# FPGA.net
KiCad netlist of a schematic drawn in Altium Designer
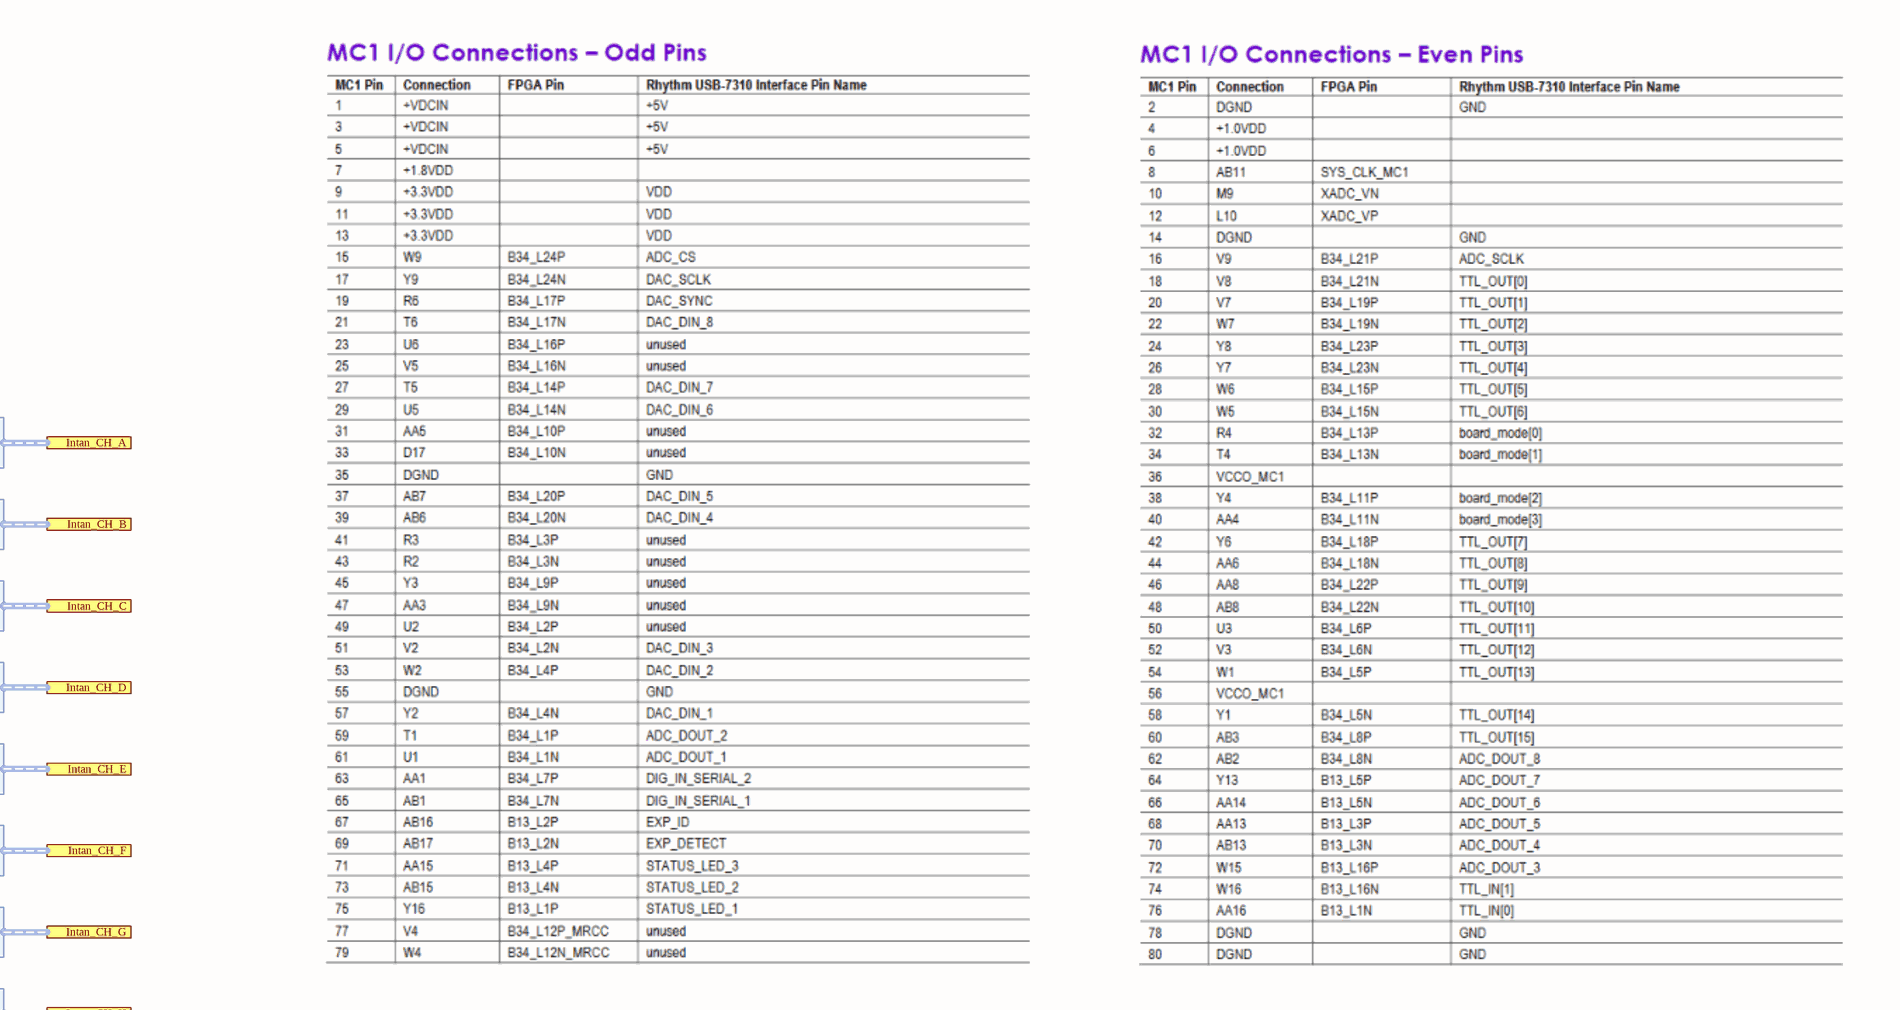
[diagram p0: FPGA.SchDoc, top right]
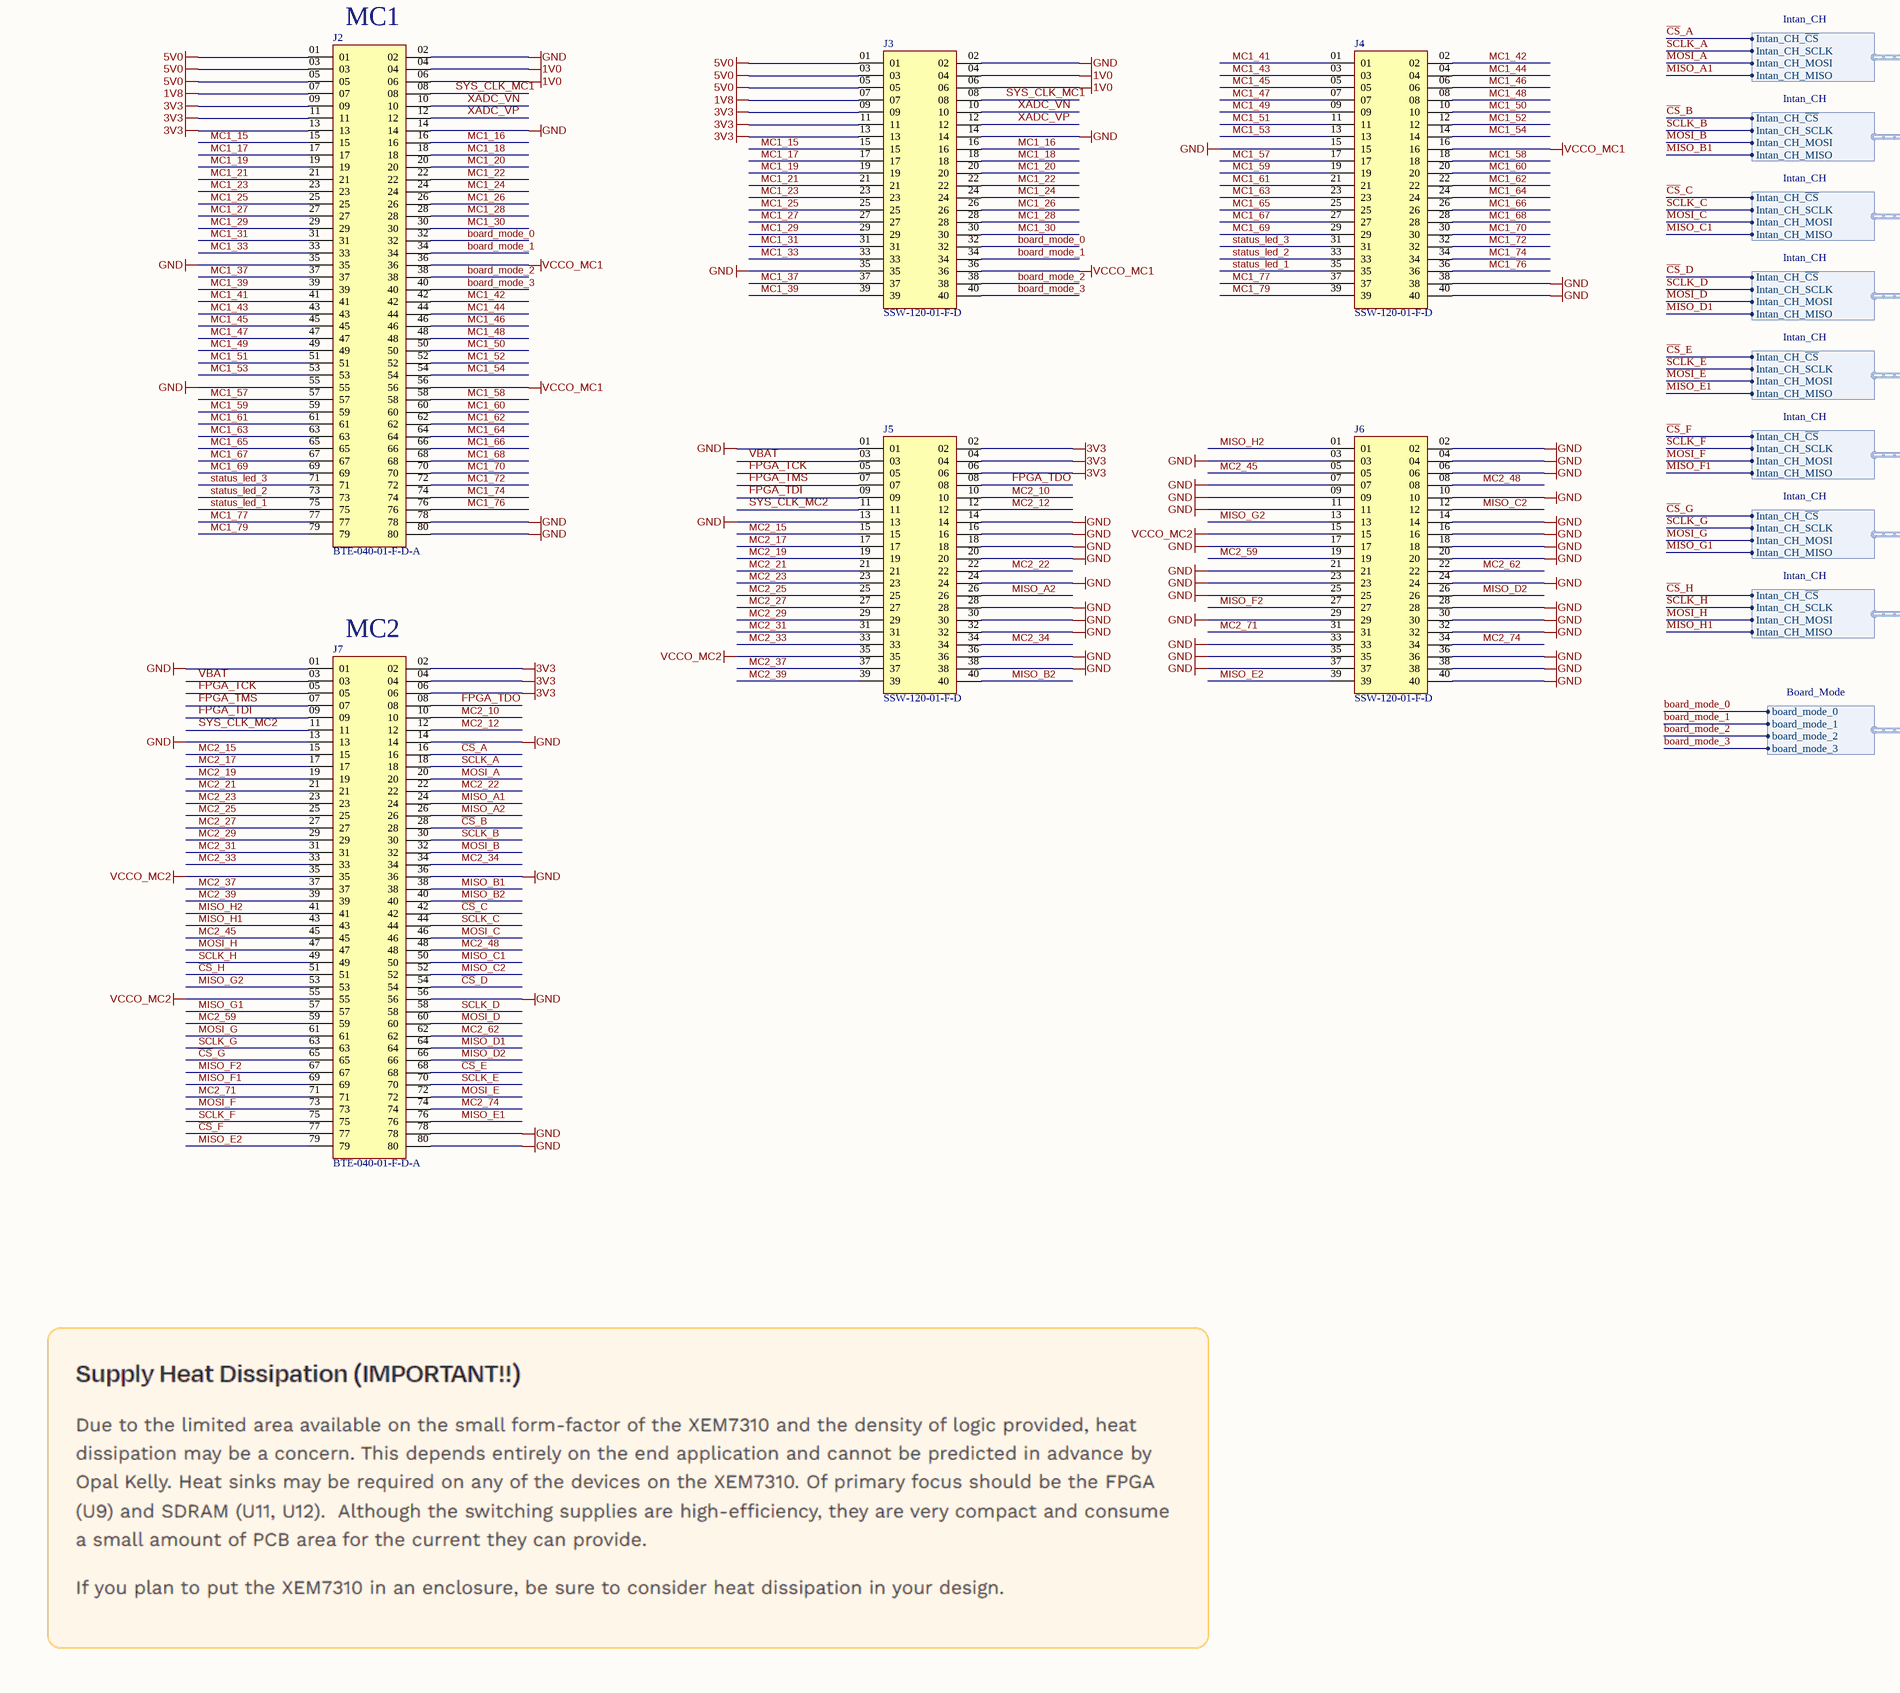
[diagram p1: FPGA.SchDoc, bottom left]
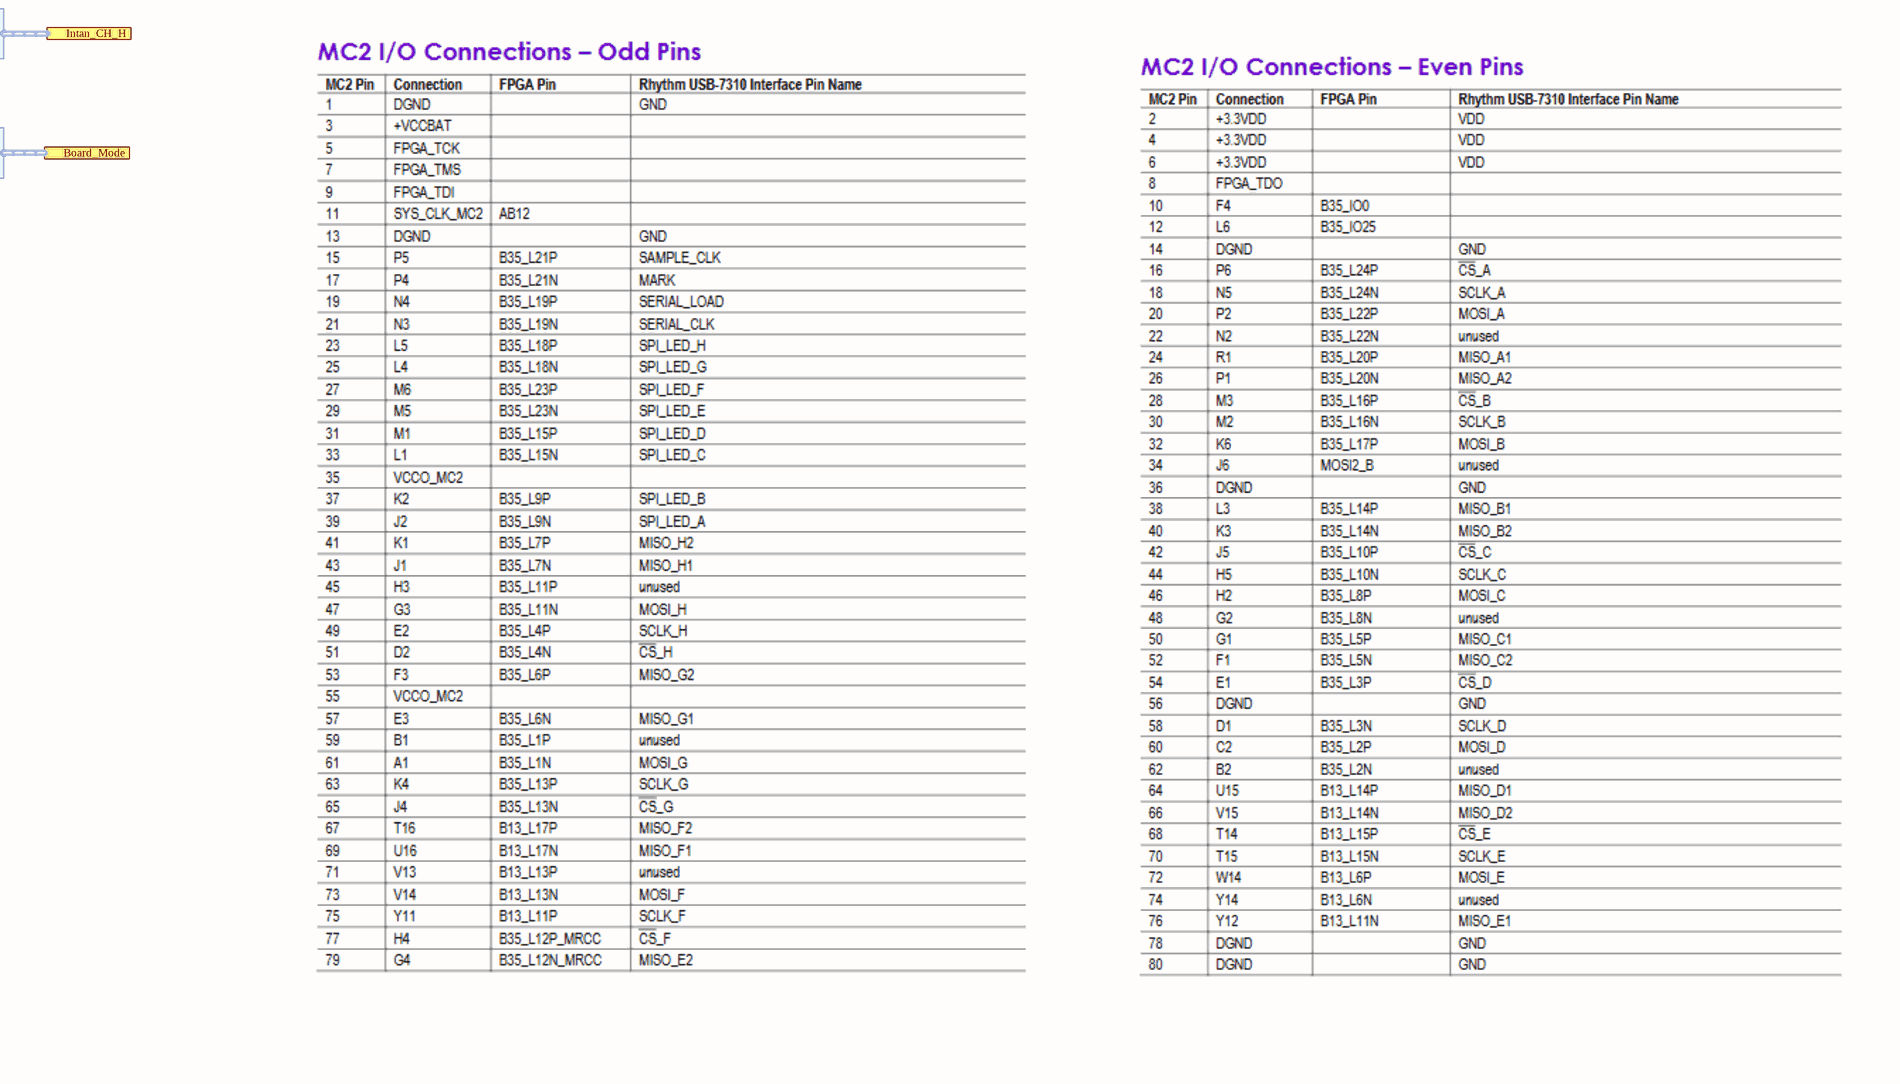
[diagram p2: FPGA.SchDoc, bottom right]

(export (version "E")
  (design (tool "Eeschema 10.0.6"))
  (components
    (comp (ref "J2")
      (value "BTE-040-01-F-D-A")
      (footprint "SAMTEC_BTE-040-01-F-D-A")
      (description "80 Position Connector Header, Outer Shroud Contacts Surface Mount Gold")
      (fields (field (name "MF") "Samtec"))
      (libsource (lib "Connectors") (part "CON_FPGA_SMD"))
    )
    (comp (ref "J3")
      (value "SSW-120-01-F-D")
      (footprint "SAMTEC_SSW-120-01-F-D")
      (description "40 Position Receptacle Connector 0.100\" (2.54mm) Through Hole Gold")
      (fields (field (name "MF") "Samtec"))
      (libsource (lib "Connectors") (part "CON_HEADF_2X20"))
    )
    (comp (ref "J4")
      (value "SSW-120-01-F-D")
      (footprint "SAMTEC_SSW-120-01-F-D")
      (description "40 Position Receptacle Connector 0.100\" (2.54mm) Through Hole Gold")
      (fields (field (name "MF") "Samtec"))
      (libsource (lib "Connectors") (part "CON_HEADF_2X20"))
    )
    (comp (ref "J5")
      (value "SSW-120-01-F-D")
      (footprint "SAMTEC_SSW-120-01-F-D")
      (description "40 Position Receptacle Connector 0.100\" (2.54mm) Through Hole Gold")
      (fields (field (name "MF") "Samtec"))
      (libsource (lib "Connectors") (part "CON_HEADF_2X20"))
    )
    (comp (ref "J6")
      (value "SSW-120-01-F-D")
      (footprint "SAMTEC_SSW-120-01-F-D")
      (description "40 Position Receptacle Connector 0.100\" (2.54mm) Through Hole Gold")
      (fields (field (name "MF") "Samtec"))
      (libsource (lib "Connectors") (part "CON_HEADF_2X20"))
    )
    (comp (ref "J7")
      (value "BTE-040-01-F-D-A")
      (footprint "SAMTEC_BTE-040-01-F-D-A")
      (description "80 Position Connector Header, Outer Shroud Contacts Surface Mount Gold")
      (fields (field (name "MF") "Samtec"))
      (libsource (lib "Connectors") (part "CON_FPGA_SMD"))
    )
  )
  (nets
    (net (code "3") (name "/FPGA_TCK") (class "Default")
      (node (ref "J5") (pin "05") (pinfunction "05_05") (pintype "passive"))
      (node (ref "J7") (pin "05") (pinfunction "05_05") (pintype "passive"))
    )
    (net (code "4") (name "/FPGA_TDI") (class "Default")
      (node (ref "J5") (pin "09") (pinfunction "09_09") (pintype "passive"))
      (node (ref "J7") (pin "09") (pinfunction "09_09") (pintype "passive"))
    )
    (net (code "5") (name "/FPGA_TDO") (class "Default")
      (node (ref "J5") (pin "08") (pinfunction "08_08") (pintype "passive"))
      (node (ref "J7") (pin "08") (pinfunction "08_08") (pintype "passive"))
    )
    (net (code "6") (name "/FPGA_TMS") (class "Default")
      (node (ref "J5") (pin "07") (pinfunction "07_07") (pintype "passive"))
      (node (ref "J7") (pin "07") (pinfunction "07_07") (pintype "passive"))
    )
    (net (code "7") (name "/MC1_15") (class "Default")
      (node (ref "J2") (pin "15") (pinfunction "15_15") (pintype "passive"))
      (node (ref "J3") (pin "15") (pinfunction "15_15") (pintype "passive"))
    )
    (net (code "8") (name "/MC1_16") (class "Default")
      (node (ref "J2") (pin "16") (pinfunction "16_16") (pintype "passive"))
      (node (ref "J3") (pin "16") (pinfunction "16_16") (pintype "passive"))
    )
    (net (code "9") (name "/MC1_17") (class "Default")
      (node (ref "J2") (pin "17") (pinfunction "17_17") (pintype "passive"))
      (node (ref "J3") (pin "17") (pinfunction "17_17") (pintype "passive"))
    )
    (net (code "10") (name "/MC1_18") (class "Default")
      (node (ref "J2") (pin "18") (pinfunction "18_18") (pintype "passive"))
      (node (ref "J3") (pin "18") (pinfunction "18_18") (pintype "passive"))
    )
    (net (code "11") (name "/MC1_19") (class "Default")
      (node (ref "J2") (pin "19") (pinfunction "19_19") (pintype "passive"))
      (node (ref "J3") (pin "19") (pinfunction "19_19") (pintype "passive"))
    )
    (net (code "12") (name "/MC1_20") (class "Default")
      (node (ref "J2") (pin "20") (pinfunction "20_20") (pintype "passive"))
      (node (ref "J3") (pin "20") (pinfunction "20_20") (pintype "passive"))
    )
    (net (code "13") (name "/MC1_21") (class "Default")
      (node (ref "J2") (pin "21") (pinfunction "21_21") (pintype "passive"))
      (node (ref "J3") (pin "21") (pinfunction "21_21") (pintype "passive"))
    )
    (net (code "14") (name "/MC1_22") (class "Default")
      (node (ref "J2") (pin "22") (pinfunction "22_22") (pintype "passive"))
      (node (ref "J3") (pin "22") (pinfunction "22_22") (pintype "passive"))
    )
    (net (code "15") (name "/MC1_23") (class "Default")
      (node (ref "J2") (pin "23") (pinfunction "23_23") (pintype "passive"))
      (node (ref "J3") (pin "23") (pinfunction "23_23") (pintype "passive"))
    )
    (net (code "16") (name "/MC1_24") (class "Default")
      (node (ref "J2") (pin "24") (pinfunction "24_24") (pintype "passive"))
      (node (ref "J3") (pin "24") (pinfunction "24_24") (pintype "passive"))
    )
    (net (code "17") (name "/MC1_25") (class "Default")
      (node (ref "J2") (pin "25") (pinfunction "25_25") (pintype "passive"))
      (node (ref "J3") (pin "25") (pinfunction "25_25") (pintype "passive"))
    )
    (net (code "18") (name "/MC1_26") (class "Default")
      (node (ref "J2") (pin "26") (pinfunction "26_26") (pintype "passive"))
      (node (ref "J3") (pin "26") (pinfunction "26_26") (pintype "passive"))
    )
    (net (code "19") (name "/MC1_27") (class "Default")
      (node (ref "J2") (pin "27") (pinfunction "27_27") (pintype "passive"))
      (node (ref "J3") (pin "27") (pinfunction "27_27") (pintype "passive"))
    )
    (net (code "20") (name "/MC1_28") (class "Default")
      (node (ref "J2") (pin "28") (pinfunction "28_28") (pintype "passive"))
      (node (ref "J3") (pin "28") (pinfunction "28_28") (pintype "passive"))
    )
    (net (code "21") (name "/MC1_29") (class "Default")
      (node (ref "J2") (pin "29") (pinfunction "29_29") (pintype "passive"))
      (node (ref "J3") (pin "29") (pinfunction "29_29") (pintype "passive"))
    )
    (net (code "22") (name "/MC1_30") (class "Default")
      (node (ref "J2") (pin "30") (pinfunction "30_30") (pintype "passive"))
      (node (ref "J3") (pin "30") (pinfunction "30_30") (pintype "passive"))
    )
    (net (code "23") (name "/MC1_31") (class "Default")
      (node (ref "J2") (pin "31") (pinfunction "31_31") (pintype "passive"))
      (node (ref "J3") (pin "31") (pinfunction "31_31") (pintype "passive"))
    )
    (net (code "24") (name "/MC1_33") (class "Default")
      (node (ref "J2") (pin "33") (pinfunction "33_33") (pintype "passive"))
      (node (ref "J3") (pin "33") (pinfunction "33_33") (pintype "passive"))
    )
    (net (code "25") (name "/MC1_37") (class "Default")
      (node (ref "J2") (pin "37") (pinfunction "37_37") (pintype "passive"))
      (node (ref "J3") (pin "37") (pinfunction "37_37") (pintype "passive"))
    )
    (net (code "26") (name "/MC1_39") (class "Default")
      (node (ref "J2") (pin "39") (pinfunction "39_39") (pintype "passive"))
      (node (ref "J3") (pin "39") (pinfunction "39_39") (pintype "passive"))
    )
    (net (code "27") (name "/MC1_41") (class "Default")
      (node (ref "J2") (pin "41") (pinfunction "41_41") (pintype "passive"))
      (node (ref "J4") (pin "01") (pinfunction "01_01") (pintype "passive"))
    )
    (net (code "28") (name "/MC1_42") (class "Default")
      (node (ref "J2") (pin "42") (pinfunction "42_42") (pintype "passive"))
      (node (ref "J4") (pin "02") (pinfunction "02_02") (pintype "passive"))
    )
    (net (code "29") (name "/MC1_43") (class "Default")
      (node (ref "J2") (pin "43") (pinfunction "43_43") (pintype "passive"))
      (node (ref "J4") (pin "03") (pinfunction "03_03") (pintype "passive"))
    )
    (net (code "30") (name "/MC1_44") (class "Default")
      (node (ref "J2") (pin "44") (pinfunction "44_44") (pintype "passive"))
      (node (ref "J4") (pin "04") (pinfunction "04_04") (pintype "passive"))
    )
    (net (code "31") (name "/MC1_45") (class "Default")
      (node (ref "J2") (pin "45") (pinfunction "45_45") (pintype "passive"))
      (node (ref "J4") (pin "05") (pinfunction "05_05") (pintype "passive"))
    )
    (net (code "32") (name "/MC1_46") (class "Default")
      (node (ref "J2") (pin "46") (pinfunction "46_46") (pintype "passive"))
      (node (ref "J4") (pin "06") (pinfunction "06_06") (pintype "passive"))
    )
    (net (code "33") (name "/MC1_47") (class "Default")
      (node (ref "J2") (pin "47") (pinfunction "47_47") (pintype "passive"))
      (node (ref "J4") (pin "07") (pinfunction "07_07") (pintype "passive"))
    )
    (net (code "34") (name "/MC1_48") (class "Default")
      (node (ref "J2") (pin "48") (pinfunction "48_48") (pintype "passive"))
      (node (ref "J4") (pin "08") (pinfunction "08_08") (pintype "passive"))
    )
    (net (code "35") (name "/MC1_49") (class "Default")
      (node (ref "J2") (pin "49") (pinfunction "49_49") (pintype "passive"))
      (node (ref "J4") (pin "09") (pinfunction "09_09") (pintype "passive"))
    )
    (net (code "36") (name "/MC1_50") (class "Default")
      (node (ref "J2") (pin "50") (pinfunction "50_50") (pintype "passive"))
      (node (ref "J4") (pin "10") (pinfunction "10_10") (pintype "passive"))
    )
    (net (code "37") (name "/MC1_51") (class "Default")
      (node (ref "J2") (pin "51") (pinfunction "51_51") (pintype "passive"))
      (node (ref "J4") (pin "11") (pinfunction "11_11") (pintype "passive"))
    )
    (net (code "38") (name "/MC1_52") (class "Default")
      (node (ref "J2") (pin "52") (pinfunction "52_52") (pintype "passive"))
      (node (ref "J4") (pin "12") (pinfunction "12_12") (pintype "passive"))
    )
    (net (code "39") (name "/MC1_53") (class "Default")
      (node (ref "J2") (pin "53") (pinfunction "53_53") (pintype "passive"))
      (node (ref "J4") (pin "13") (pinfunction "13_13") (pintype "passive"))
    )
    (net (code "40") (name "/MC1_54") (class "Default")
      (node (ref "J2") (pin "54") (pinfunction "54_54") (pintype "passive"))
      (node (ref "J4") (pin "14") (pinfunction "14_14") (pintype "passive"))
    )
    (net (code "41") (name "/MC1_57") (class "Default")
      (node (ref "J2") (pin "57") (pinfunction "57_57") (pintype "passive"))
      (node (ref "J4") (pin "17") (pinfunction "17_17") (pintype "passive"))
    )
    (net (code "42") (name "/MC1_58") (class "Default")
      (node (ref "J2") (pin "58") (pinfunction "58_58") (pintype "passive"))
      (node (ref "J4") (pin "18") (pinfunction "18_18") (pintype "passive"))
    )
    (net (code "43") (name "/MC1_59") (class "Default")
      (node (ref "J2") (pin "59") (pinfunction "59_59") (pintype "passive"))
      (node (ref "J4") (pin "19") (pinfunction "19_19") (pintype "passive"))
    )
    (net (code "44") (name "/MC1_60") (class "Default")
      (node (ref "J2") (pin "60") (pinfunction "60_60") (pintype "passive"))
      (node (ref "J4") (pin "20") (pinfunction "20_20") (pintype "passive"))
    )
    (net (code "45") (name "/MC1_61") (class "Default")
      (node (ref "J2") (pin "61") (pinfunction "61_61") (pintype "passive"))
      (node (ref "J4") (pin "21") (pinfunction "21_21") (pintype "passive"))
    )
    (net (code "46") (name "/MC1_62") (class "Default")
      (node (ref "J2") (pin "62") (pinfunction "62_62") (pintype "passive"))
      (node (ref "J4") (pin "22") (pinfunction "22_22") (pintype "passive"))
    )
    (net (code "47") (name "/MC1_63") (class "Default")
      (node (ref "J2") (pin "63") (pinfunction "63_63") (pintype "passive"))
      (node (ref "J4") (pin "23") (pinfunction "23_23") (pintype "passive"))
    )
    (net (code "48") (name "/MC1_64") (class "Default")
      (node (ref "J2") (pin "64") (pinfunction "64_64") (pintype "passive"))
      (node (ref "J4") (pin "24") (pinfunction "24_24") (pintype "passive"))
    )
    (net (code "49") (name "/MC1_65") (class "Default")
      (node (ref "J2") (pin "65") (pinfunction "65_65") (pintype "passive"))
      (node (ref "J4") (pin "25") (pinfunction "25_25") (pintype "passive"))
    )
    (net (code "50") (name "/MC1_66") (class "Default")
      (node (ref "J2") (pin "66") (pinfunction "66_66") (pintype "passive"))
      (node (ref "J4") (pin "26") (pinfunction "26_26") (pintype "passive"))
    )
    (net (code "51") (name "/MC1_67") (class "Default")
      (node (ref "J2") (pin "67") (pinfunction "67_67") (pintype "passive"))
      (node (ref "J4") (pin "27") (pinfunction "27_27") (pintype "passive"))
    )
    (net (code "52") (name "/MC1_68") (class "Default")
      (node (ref "J2") (pin "68") (pinfunction "68_68") (pintype "passive"))
      (node (ref "J4") (pin "28") (pinfunction "28_28") (pintype "passive"))
    )
    (net (code "53") (name "/MC1_69") (class "Default")
      (node (ref "J2") (pin "69") (pinfunction "69_69") (pintype "passive"))
      (node (ref "J4") (pin "29") (pinfunction "29_29") (pintype "passive"))
    )
    (net (code "54") (name "/MC1_70") (class "Default")
      (node (ref "J2") (pin "70") (pinfunction "70_70") (pintype "passive"))
      (node (ref "J4") (pin "30") (pinfunction "30_30") (pintype "passive"))
    )
    (net (code "55") (name "/MC1_72") (class "Default")
      (node (ref "J2") (pin "72") (pinfunction "72_72") (pintype "passive"))
      (node (ref "J4") (pin "32") (pinfunction "32_32") (pintype "passive"))
    )
    (net (code "56") (name "/MC1_74") (class "Default")
      (node (ref "J2") (pin "74") (pinfunction "74_74") (pintype "passive"))
      (node (ref "J4") (pin "34") (pinfunction "34_34") (pintype "passive"))
    )
    (net (code "57") (name "/MC1_76") (class "Default")
      (node (ref "J2") (pin "76") (pinfunction "76_76") (pintype "passive"))
      (node (ref "J4") (pin "36") (pinfunction "36_36") (pintype "passive"))
    )
    (net (code "58") (name "/MC1_77") (class "Default")
      (node (ref "J2") (pin "77") (pinfunction "77_77") (pintype "passive"))
      (node (ref "J4") (pin "37") (pinfunction "37_37") (pintype "passive"))
    )
    (net (code "59") (name "/MC1_79") (class "Default")
      (node (ref "J2") (pin "79") (pinfunction "79_79") (pintype "passive"))
      (node (ref "J4") (pin "39") (pinfunction "39_39") (pintype "passive"))
    )
    (net (code "60") (name "/MC2_10") (class "Default")
      (node (ref "J5") (pin "10") (pinfunction "10_10") (pintype "passive"))
      (node (ref "J7") (pin "10") (pinfunction "10_10") (pintype "passive"))
    )
    (net (code "61") (name "/MC2_12") (class "Default")
      (node (ref "J5") (pin "12") (pinfunction "12_12") (pintype "passive"))
      (node (ref "J7") (pin "12") (pinfunction "12_12") (pintype "passive"))
    )
    (net (code "62") (name "/MC2_15") (class "Default")
      (node (ref "J5") (pin "15") (pinfunction "15_15") (pintype "passive"))
      (node (ref "J7") (pin "15") (pinfunction "15_15") (pintype "passive"))
    )
    (net (code "63") (name "/MC2_17") (class "Default")
      (node (ref "J5") (pin "17") (pinfunction "17_17") (pintype "passive"))
      (node (ref "J7") (pin "17") (pinfunction "17_17") (pintype "passive"))
    )
    (net (code "64") (name "/MC2_19") (class "Default")
      (node (ref "J5") (pin "19") (pinfunction "19_19") (pintype "passive"))
      (node (ref "J7") (pin "19") (pinfunction "19_19") (pintype "passive"))
    )
    (net (code "65") (name "/MC2_21") (class "Default")
      (node (ref "J5") (pin "21") (pinfunction "21_21") (pintype "passive"))
      (node (ref "J7") (pin "21") (pinfunction "21_21") (pintype "passive"))
    )
    (net (code "66") (name "/MC2_22") (class "Default")
      (node (ref "J5") (pin "22") (pinfunction "22_22") (pintype "passive"))
      (node (ref "J7") (pin "22") (pinfunction "22_22") (pintype "passive"))
    )
    (net (code "67") (name "/MC2_23") (class "Default")
      (node (ref "J5") (pin "23") (pinfunction "23_23") (pintype "passive"))
      (node (ref "J7") (pin "23") (pinfunction "23_23") (pintype "passive"))
    )
    (net (code "68") (name "/MC2_25") (class "Default")
      (node (ref "J5") (pin "25") (pinfunction "25_25") (pintype "passive"))
      (node (ref "J7") (pin "25") (pinfunction "25_25") (pintype "passive"))
    )
    (net (code "69") (name "/MC2_27") (class "Default")
      (node (ref "J5") (pin "27") (pinfunction "27_27") (pintype "passive"))
      (node (ref "J7") (pin "27") (pinfunction "27_27") (pintype "passive"))
    )
    (net (code "70") (name "/MC2_29") (class "Default")
      (node (ref "J5") (pin "29") (pinfunction "29_29") (pintype "passive"))
      (node (ref "J7") (pin "29") (pinfunction "29_29") (pintype "passive"))
    )
    (net (code "71") (name "/MC2_31") (class "Default")
      (node (ref "J5") (pin "31") (pinfunction "31_31") (pintype "passive"))
      (node (ref "J7") (pin "31") (pinfunction "31_31") (pintype "passive"))
    )
    (net (code "72") (name "/MC2_33") (class "Default")
      (node (ref "J5") (pin "33") (pinfunction "33_33") (pintype "passive"))
      (node (ref "J7") (pin "33") (pinfunction "33_33") (pintype "passive"))
    )
    (net (code "73") (name "/MC2_34") (class "Default")
      (node (ref "J5") (pin "34") (pinfunction "34_34") (pintype "passive"))
      (node (ref "J7") (pin "34") (pinfunction "34_34") (pintype "passive"))
    )
    (net (code "74") (name "/MC2_37") (class "Default")
      (node (ref "J5") (pin "37") (pinfunction "37_37") (pintype "passive"))
      (node (ref "J7") (pin "37") (pinfunction "37_37") (pintype "passive"))
    )
    (net (code "75") (name "/MC2_39") (class "Default")
      (node (ref "J5") (pin "39") (pinfunction "39_39") (pintype "passive"))
      (node (ref "J7") (pin "39") (pinfunction "39_39") (pintype "passive"))
    )
    (net (code "76") (name "/MC2_45") (class "Default")
      (node (ref "J6") (pin "05") (pinfunction "05_05") (pintype "passive"))
      (node (ref "J7") (pin "45") (pinfunction "45_45") (pintype "passive"))
    )
    (net (code "77") (name "/MC2_48") (class "Default")
      (node (ref "J6") (pin "08") (pinfunction "08_08") (pintype "passive"))
      (node (ref "J7") (pin "48") (pinfunction "48_48") (pintype "passive"))
    )
    (net (code "78") (name "/MC2_59") (class "Default")
      (node (ref "J6") (pin "19") (pinfunction "19_19") (pintype "passive"))
      (node (ref "J7") (pin "59") (pinfunction "59_59") (pintype "passive"))
    )
    (net (code "79") (name "/MC2_62") (class "Default")
      (node (ref "J6") (pin "22") (pinfunction "22_22") (pintype "passive"))
      (node (ref "J7") (pin "62") (pinfunction "62_62") (pintype "passive"))
    )
    (net (code "80") (name "/MC2_71") (class "Default")
      (node (ref "J6") (pin "31") (pinfunction "31_31") (pintype "passive"))
      (node (ref "J7") (pin "71") (pinfunction "71_71") (pintype "passive"))
    )
    (net (code "81") (name "/MC2_74") (class "Default")
      (node (ref "J6") (pin "34") (pinfunction "34_34") (pintype "passive"))
      (node (ref "J7") (pin "74") (pinfunction "74_74") (pintype "passive"))
    )
    (net (code "82") (name "/MISO_A1") (class "Default")
      (node (ref "J7") (pin "24") (pinfunction "24_24") (pintype "passive"))
    )
    (net (code "83") (name "/MISO_A2") (class "Default")
      (node (ref "J5") (pin "26") (pinfunction "26_26") (pintype "passive"))
      (node (ref "J7") (pin "26") (pinfunction "26_26") (pintype "passive"))
    )
    (net (code "84") (name "/MISO_B1") (class "Default")
      (node (ref "J7") (pin "38") (pinfunction "38_38") (pintype "passive"))
    )
    (net (code "85") (name "/MISO_B2") (class "Default")
      (node (ref "J5") (pin "40") (pinfunction "40_40") (pintype "passive"))
      (node (ref "J7") (pin "40") (pinfunction "40_40") (pintype "passive"))
    )
    (net (code "86") (name "/MISO_C1") (class "Default")
      (node (ref "J7") (pin "50") (pinfunction "50_50") (pintype "passive"))
    )
    (net (code "87") (name "/MISO_C2") (class "Default")
      (node (ref "J6") (pin "12") (pinfunction "12_12") (pintype "passive"))
      (node (ref "J7") (pin "52") (pinfunction "52_52") (pintype "passive"))
    )
    (net (code "88") (name "/MISO_D1") (class "Default")
      (node (ref "J7") (pin "64") (pinfunction "64_64") (pintype "passive"))
    )
    (net (code "89") (name "/MISO_D2") (class "Default")
      (node (ref "J6") (pin "26") (pinfunction "26_26") (pintype "passive"))
      (node (ref "J7") (pin "66") (pinfunction "66_66") (pintype "passive"))
    )
    (net (code "90") (name "/MISO_E1") (class "Default")
      (node (ref "J7") (pin "76") (pinfunction "76_76") (pintype "passive"))
    )
    (net (code "91") (name "/MISO_E2") (class "Default")
      (node (ref "J6") (pin "39") (pinfunction "39_39") (pintype "passive"))
      (node (ref "J7") (pin "79") (pinfunction "79_79") (pintype "passive"))
    )
    (net (code "92") (name "/MISO_F1") (class "Default")
      (node (ref "J7") (pin "69") (pinfunction "69_69") (pintype "passive"))
    )
    (net (code "93") (name "/MISO_F2") (class "Default")
      (node (ref "J6") (pin "27") (pinfunction "27_27") (pintype "passive"))
      (node (ref "J7") (pin "67") (pinfunction "67_67") (pintype "passive"))
    )
    (net (code "94") (name "/MISO_G1") (class "Default")
      (node (ref "J7") (pin "57") (pinfunction "57_57") (pintype "passive"))
    )
    (net (code "95") (name "/MISO_G2") (class "Default")
      (node (ref "J6") (pin "13") (pinfunction "13_13") (pintype "passive"))
      (node (ref "J7") (pin "53") (pinfunction "53_53") (pintype "passive"))
    )
    (net (code "96") (name "/MISO_H1") (class "Default")
      (node (ref "J7") (pin "43") (pinfunction "43_43") (pintype "passive"))
    )
    (net (code "97") (name "/MISO_H2") (class "Default")
      (node (ref "J6") (pin "01") (pinfunction "01_01") (pintype "passive"))
      (node (ref "J7") (pin "41") (pinfunction "41_41") (pintype "passive"))
    )
    (net (code "98") (name "/MOSI_A") (class "Default")
      (node (ref "J7") (pin "20") (pinfunction "20_20") (pintype "passive"))
    )
    (net (code "99") (name "/MOSI_B") (class "Default")
      (node (ref "J7") (pin "32") (pinfunction "32_32") (pintype "passive"))
    )
    (net (code "100") (name "/MOSI_C") (class "Default")
      (node (ref "J7") (pin "46") (pinfunction "46_46") (pintype "passive"))
    )
    (net (code "101") (name "/MOSI_D") (class "Default")
      (node (ref "J7") (pin "60") (pinfunction "60_60") (pintype "passive"))
    )
    (net (code "102") (name "/MOSI_E") (class "Default")
      (node (ref "J7") (pin "72") (pinfunction "72_72") (pintype "passive"))
    )
    (net (code "103") (name "/MOSI_F") (class "Default")
      (node (ref "J7") (pin "73") (pinfunction "73_73") (pintype "passive"))
    )
    (net (code "104") (name "/MOSI_G") (class "Default")
      (node (ref "J7") (pin "61") (pinfunction "61_61") (pintype "passive"))
    )
    (net (code "105") (name "/MOSI_H") (class "Default")
      (node (ref "J7") (pin "47") (pinfunction "47_47") (pintype "passive"))
    )
    (net (code "106") (name "/SCLK_A") (class "Default")
      (node (ref "J7") (pin "18") (pinfunction "18_18") (pintype "passive"))
    )
    (net (code "107") (name "/SCLK_B") (class "Default")
      (node (ref "J7") (pin "30") (pinfunction "30_30") (pintype "passive"))
    )
    (net (code "108") (name "/SCLK_C") (class "Default")
      (node (ref "J7") (pin "44") (pinfunction "44_44") (pintype "passive"))
    )
    (net (code "109") (name "/SCLK_D") (class "Default")
      (node (ref "J7") (pin "58") (pinfunction "58_58") (pintype "passive"))
    )
    (net (code "110") (name "/SCLK_E") (class "Default")
      (node (ref "J7") (pin "70") (pinfunction "70_70") (pintype "passive"))
    )
    (net (code "111") (name "/SCLK_F") (class "Default")
      (node (ref "J7") (pin "75") (pinfunction "75_75") (pintype "passive"))
    )
    (net (code "112") (name "/SCLK_G") (class "Default")
      (node (ref "J7") (pin "63") (pinfunction "63_63") (pintype "passive"))
    )
    (net (code "113") (name "/SCLK_H") (class "Default")
      (node (ref "J7") (pin "49") (pinfunction "49_49") (pintype "passive"))
    )
    (net (code "114") (name "/SYS_CLK_MC1") (class "Default")
      (node (ref "J2") (pin "08") (pinfunction "08_08") (pintype "passive"))
      (node (ref "J3") (pin "08") (pinfunction "08_08") (pintype "passive"))
    )
    (net (code "115") (name "/SYS_CLK_MC2") (class "Default")
      (node (ref "J5") (pin "11") (pinfunction "11_11") (pintype "passive"))
      (node (ref "J7") (pin "11") (pinfunction "11_11") (pintype "passive"))
    )
    (net (code "116") (name "/VBAT") (class "Default")
      (node (ref "J5") (pin "03") (pinfunction "03_03") (pintype "passive"))
      (node (ref "J7") (pin "03") (pinfunction "03_03") (pintype "passive"))
    )
    (net (code "117") (name "/XADC_VN") (class "Default")
      (node (ref "J2") (pin "10") (pinfunction "10_10") (pintype "passive"))
      (node (ref "J3") (pin "10") (pinfunction "10_10") (pintype "passive"))
    )
    (net (code "118") (name "/XADC_VP") (class "Default")
      (node (ref "J2") (pin "12") (pinfunction "12_12") (pintype "passive"))
      (node (ref "J3") (pin "12") (pinfunction "12_12") (pintype "passive"))
    )
    (net (code "119") (name "/board_mode_0") (class "Default")
      (node (ref "J2") (pin "32") (pinfunction "32_32") (pintype "passive"))
      (node (ref "J3") (pin "32") (pinfunction "32_32") (pintype "passive"))
    )
    (net (code "120") (name "/board_mode_1") (class "Default")
      (node (ref "J2") (pin "34") (pinfunction "34_34") (pintype "passive"))
      (node (ref "J3") (pin "34") (pinfunction "34_34") (pintype "passive"))
    )
    (net (code "121") (name "/board_mode_2") (class "Default")
      (node (ref "J2") (pin "38") (pinfunction "38_38") (pintype "passive"))
      (node (ref "J3") (pin "38") (pinfunction "38_38") (pintype "passive"))
    )
    (net (code "122") (name "/board_mode_3") (class "Default")
      (node (ref "J2") (pin "40") (pinfunction "40_40") (pintype "passive"))
      (node (ref "J3") (pin "40") (pinfunction "40_40") (pintype "passive"))
    )
    (net (code "123") (name "/status_led_1") (class "Default")
      (node (ref "J2") (pin "75") (pinfunction "75_75") (pintype "passive"))
      (node (ref "J4") (pin "35") (pinfunction "35_35") (pintype "passive"))
    )
    (net (code "124") (name "/status_led_2") (class "Default")
      (node (ref "J2") (pin "73") (pinfunction "73_73") (pintype "passive"))
      (node (ref "J4") (pin "33") (pinfunction "33_33") (pintype "passive"))
    )
    (net (code "125") (name "/status_led_3") (class "Default")
      (node (ref "J2") (pin "71") (pinfunction "71_71") (pintype "passive"))
      (node (ref "J4") (pin "31") (pinfunction "31_31") (pintype "passive"))
    )
    (net (code "128") (name "/~{CS}_A") (class "Default")
      (node (ref "J7") (pin "16") (pinfunction "16_16") (pintype "passive"))
    )
    (net (code "129") (name "/~{CS}_B") (class "Default")
      (node (ref "J7") (pin "28") (pinfunction "28_28") (pintype "passive"))
    )
    (net (code "130") (name "/~{CS}_C") (class "Default")
      (node (ref "J7") (pin "42") (pinfunction "42_42") (pintype "passive"))
    )
    (net (code "131") (name "/~{CS}_D") (class "Default")
      (node (ref "J7") (pin "54") (pinfunction "54_54") (pintype "passive"))
    )
    (net (code "132") (name "/~{CS}_E") (class "Default")
      (node (ref "J7") (pin "68") (pinfunction "68_68") (pintype "passive"))
    )
    (net (code "133") (name "/~{CS}_F") (class "Default")
      (node (ref "J7") (pin "77") (pinfunction "77_77") (pintype "passive"))
    )
    (net (code "134") (name "/~{CS}_G") (class "Default")
      (node (ref "J7") (pin "65") (pinfunction "65_65") (pintype "passive"))
    )
    (net (code "135") (name "/~{CS}_H") (class "Default")
      (node (ref "J7") (pin "51") (pinfunction "51_51") (pintype "passive"))
    )
    (net (code "136") (name "1V0") (class "Default")
      (node (ref "J2") (pin "04") (pinfunction "04_04") (pintype "passive"))
      (node (ref "J2") (pin "06") (pinfunction "06_06") (pintype "passive"))
      (node (ref "J3") (pin "04") (pinfunction "04_04") (pintype "passive"))
      (node (ref "J3") (pin "06") (pinfunction "06_06") (pintype "passive"))
    )
    (net (code "137") (name "1V8") (class "Default")
      (node (ref "J2") (pin "07") (pinfunction "07_07") (pintype "passive"))
      (node (ref "J3") (pin "07") (pinfunction "07_07") (pintype "passive"))
    )
    (net (code "138") (name "3V3") (class "Default")
      (node (ref "J2") (pin "09") (pinfunction "09_09") (pintype "passive"))
      (node (ref "J2") (pin "11") (pinfunction "11_11") (pintype "passive"))
      (node (ref "J2") (pin "13") (pinfunction "13_13") (pintype "passive"))
      (node (ref "J3") (pin "09") (pinfunction "09_09") (pintype "passive"))
      (node (ref "J3") (pin "11") (pinfunction "11_11") (pintype "passive"))
      (node (ref "J3") (pin "13") (pinfunction "13_13") (pintype "passive"))
      (node (ref "J5") (pin "02") (pinfunction "02_02") (pintype "passive"))
      (node (ref "J5") (pin "04") (pinfunction "04_04") (pintype "passive"))
      (node (ref "J5") (pin "06") (pinfunction "06_06") (pintype "passive"))
      (node (ref "J7") (pin "02") (pinfunction "02_02") (pintype "passive"))
      (node (ref "J7") (pin "04") (pinfunction "04_04") (pintype "passive"))
      (node (ref "J7") (pin "06") (pinfunction "06_06") (pintype "passive"))
    )
    (net (code "139") (name "5V0") (class "Default")
      (node (ref "J2") (pin "01") (pinfunction "01_01") (pintype "passive"))
      (node (ref "J2") (pin "03") (pinfunction "03_03") (pintype "passive"))
      (node (ref "J2") (pin "05") (pinfunction "05_05") (pintype "passive"))
      (node (ref "J3") (pin "01") (pinfunction "01_01") (pintype "passive"))
      (node (ref "J3") (pin "03") (pinfunction "03_03") (pintype "passive"))
      (node (ref "J3") (pin "05") (pinfunction "05_05") (pintype "passive"))
    )
    (net (code "140") (name "GND") (class "Default")
      (node (ref "J2") (pin "02") (pinfunction "02_02") (pintype "passive"))
      (node (ref "J2") (pin "14") (pinfunction "14_14") (pintype "passive"))
      (node (ref "J2") (pin "35") (pinfunction "35_35") (pintype "passive"))
      (node (ref "J2") (pin "55") (pinfunction "55_55") (pintype "passive"))
      (node (ref "J2") (pin "78") (pinfunction "78_78") (pintype "passive"))
      (node (ref "J2") (pin "80") (pinfunction "80_80") (pintype "passive"))
      (node (ref "J3") (pin "02") (pinfunction "02_02") (pintype "passive"))
      (node (ref "J3") (pin "14") (pinfunction "14_14") (pintype "passive"))
      (node (ref "J3") (pin "35") (pinfunction "35_35") (pintype "passive"))
      (node (ref "J4") (pin "15") (pinfunction "15_15") (pintype "passive"))
      (node (ref "J4") (pin "38") (pinfunction "38_38") (pintype "passive"))
      (node (ref "J4") (pin "40") (pinfunction "40_40") (pintype "passive"))
      (node (ref "J5") (pin "01") (pinfunction "01_01") (pintype "passive"))
      (node (ref "J5") (pin "13") (pinfunction "13_13") (pintype "passive"))
      (node (ref "J5") (pin "14") (pinfunction "14_14") (pintype "passive"))
      (node (ref "J5") (pin "16") (pinfunction "16_16") (pintype "passive"))
      (node (ref "J5") (pin "18") (pinfunction "18_18") (pintype "passive"))
      (node (ref "J5") (pin "20") (pinfunction "20_20") (pintype "passive"))
      (node (ref "J5") (pin "24") (pinfunction "24_24") (pintype "passive"))
      (node (ref "J5") (pin "28") (pinfunction "28_28") (pintype "passive"))
      (node (ref "J5") (pin "30") (pinfunction "30_30") (pintype "passive"))
      (node (ref "J5") (pin "32") (pinfunction "32_32") (pintype "passive"))
      (node (ref "J5") (pin "36") (pinfunction "36_36") (pintype "passive"))
      (node (ref "J5") (pin "38") (pinfunction "38_38") (pintype "passive"))
      (node (ref "J6") (pin "02") (pinfunction "02_02") (pintype "passive"))
      (node (ref "J6") (pin "03") (pinfunction "03_03") (pintype "passive"))
      (node (ref "J6") (pin "04") (pinfunction "04_04") (pintype "passive"))
      (node (ref "J6") (pin "06") (pinfunction "06_06") (pintype "passive"))
      (node (ref "J6") (pin "07") (pinfunction "07_07") (pintype "passive"))
      (node (ref "J6") (pin "09") (pinfunction "09_09") (pintype "passive"))
      (node (ref "J6") (pin "10") (pinfunction "10_10") (pintype "passive"))
      (node (ref "J6") (pin "11") (pinfunction "11_11") (pintype "passive"))
      (node (ref "J6") (pin "14") (pinfunction "14_14") (pintype "passive"))
      (node (ref "J6") (pin "16") (pinfunction "16_16") (pintype "passive"))
      (node (ref "J6") (pin "17") (pinfunction "17_17") (pintype "passive"))
      (node (ref "J6") (pin "18") (pinfunction "18_18") (pintype "passive"))
      (node (ref "J6") (pin "20") (pinfunction "20_20") (pintype "passive"))
      (node (ref "J6") (pin "21") (pinfunction "21_21") (pintype "passive"))
      (node (ref "J6") (pin "23") (pinfunction "23_23") (pintype "passive"))
      (node (ref "J6") (pin "24") (pinfunction "24_24") (pintype "passive"))
      (node (ref "J6") (pin "25") (pinfunction "25_25") (pintype "passive"))
      (node (ref "J6") (pin "28") (pinfunction "28_28") (pintype "passive"))
      (node (ref "J6") (pin "29") (pinfunction "29_29") (pintype "passive"))
      (node (ref "J6") (pin "30") (pinfunction "30_30") (pintype "passive"))
      (node (ref "J6") (pin "32") (pinfunction "32_32") (pintype "passive"))
      (node (ref "J6") (pin "33") (pinfunction "33_33") (pintype "passive"))
      (node (ref "J6") (pin "35") (pinfunction "35_35") (pintype "passive"))
      (node (ref "J6") (pin "36") (pinfunction "36_36") (pintype "passive"))
      (node (ref "J6") (pin "37") (pinfunction "37_37") (pintype "passive"))
      (node (ref "J6") (pin "38") (pinfunction "38_38") (pintype "passive"))
      (node (ref "J6") (pin "40") (pinfunction "40_40") (pintype "passive"))
      (node (ref "J7") (pin "01") (pinfunction "01_01") (pintype "passive"))
      (node (ref "J7") (pin "13") (pinfunction "13_13") (pintype "passive"))
      (node (ref "J7") (pin "14") (pinfunction "14_14") (pintype "passive"))
      (node (ref "J7") (pin "36") (pinfunction "36_36") (pintype "passive"))
      (node (ref "J7") (pin "56") (pinfunction "56_56") (pintype "passive"))
      (node (ref "J7") (pin "78") (pinfunction "78_78") (pintype "passive"))
      (node (ref "J7") (pin "80") (pinfunction "80_80") (pintype "passive"))
    )
    (net (code "141") (name "VCCO_MC1") (class "Default")
      (node (ref "J2") (pin "36") (pinfunction "36_36") (pintype "passive"))
      (node (ref "J2") (pin "56") (pinfunction "56_56") (pintype "passive"))
      (node (ref "J3") (pin "36") (pinfunction "36_36") (pintype "passive"))
      (node (ref "J4") (pin "16") (pinfunction "16_16") (pintype "passive"))
    )
    (net (code "142") (name "VCCO_MC2") (class "Default")
      (node (ref "J5") (pin "35") (pinfunction "35_35") (pintype "passive"))
      (node (ref "J6") (pin "15") (pinfunction "15_15") (pintype "passive"))
      (node (ref "J7") (pin "35") (pinfunction "35_35") (pintype "passive"))
      (node (ref "J7") (pin "55") (pinfunction "55_55") (pintype "passive"))
    )
  )
)
